# Driver1.net
KiCad netlist of a schematic drawn in Altium Designer
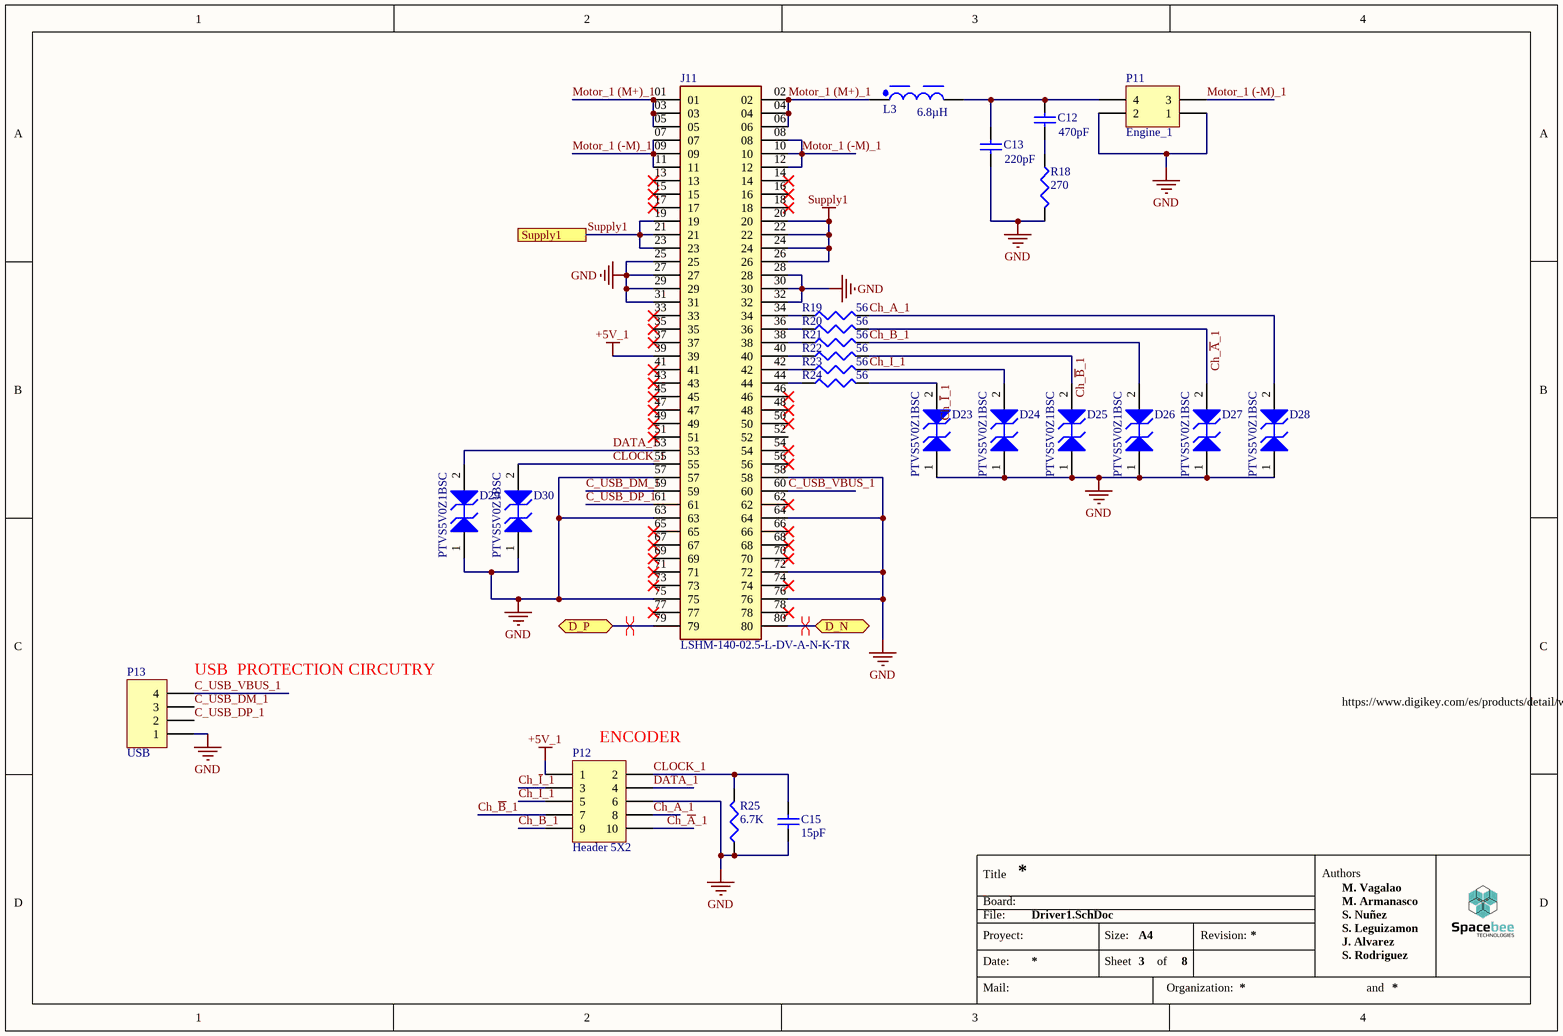
[diagram p0: Driver1.SchDoc]

(export (version "E")
  (design (tool "Eeschema 10.0.6"))
  (components
    (comp (ref "C12")
      (value "470pF")
      (footprint "1608[0603]")
      (description "Capacitor (Semiconductor SIM Model)")
      (fields (field (name "Comment") "Cap Semi") (field (name "PUBLISHER") "Altium Limited"))
      (libsource (lib "Miscellaneous Devices") (part "Cap Semi"))
    )
    (comp (ref "C13")
      (value "220pF")
      (footprint "1608[0603]")
      (description "Capacitor (Semiconductor SIM Model)")
      (fields (field (name "Comment") "Cap Semi") (field (name "PUBLISHER") "Altium Limited"))
      (libsource (lib "Miscellaneous Devices") (part "Cap Semi"))
    )
    (comp (ref "C15")
      (value "15pF")
      (footprint "6-0805_L")
      (description "Capacitor (Semiconductor SIM Model)")
      (fields (field (name "Comment") "Cap Semi") (field (name "PUBLISHER") "Altium Limited"))
      (libsource (lib "SpaceBee") (part "Cap 0805"))
    )
    (comp (ref "D23")
      (value "PTVS5V0Z1BSC")
      (footprint "SOD993B")
      (fields (field (name "MANUFACTURER") "On Semiconductor") (field (name "PARTNUMBER") "1SMB16CAT3"))
      (libsource (lib "DriverLib") (part "PTVS5V0Z1BSC"))
    )
    (comp (ref "D24")
      (value "PTVS5V0Z1BSC")
      (footprint "SOD993B")
      (fields (field (name "MANUFACTURER") "On Semiconductor") (field (name "PARTNUMBER") "1SMB16CAT3"))
      (libsource (lib "DriverLib") (part "PTVS5V0Z1BSC"))
    )
    (comp (ref "D25")
      (value "PTVS5V0Z1BSC")
      (footprint "SOD993B")
      (fields (field (name "MANUFACTURER") "On Semiconductor") (field (name "PARTNUMBER") "1SMB16CAT3"))
      (libsource (lib "DriverLib") (part "PTVS5V0Z1BSC"))
    )
    (comp (ref "D26")
      (value "PTVS5V0Z1BSC")
      (footprint "SOD993B")
      (fields (field (name "MANUFACTURER") "On Semiconductor") (field (name "PARTNUMBER") "1SMB16CAT3"))
      (libsource (lib "DriverLib") (part "PTVS5V0Z1BSC"))
    )
    (comp (ref "D27")
      (value "PTVS5V0Z1BSC")
      (footprint "SOD993B")
      (fields (field (name "MANUFACTURER") "On Semiconductor") (field (name "PARTNUMBER") "1SMB16CAT3"))
      (libsource (lib "DriverLib") (part "PTVS5V0Z1BSC"))
    )
    (comp (ref "D28")
      (value "PTVS5V0Z1BSC")
      (footprint "SOD993B")
      (fields (field (name "MANUFACTURER") "On Semiconductor") (field (name "PARTNUMBER") "1SMB16CAT3"))
      (libsource (lib "DriverLib") (part "PTVS5V0Z1BSC"))
    )
    (comp (ref "D29")
      (value "PTVS5V0Z1BSC")
      (footprint "SOD993B")
      (fields (field (name "MANUFACTURER") "On Semiconductor") (field (name "PARTNUMBER") "1SMB16CAT3"))
      (libsource (lib "DriverLib") (part "PTVS5V0Z1BSC"))
    )
    (comp (ref "D30")
      (value "PTVS5V0Z1BSC")
      (footprint "SOD993B")
      (fields (field (name "MANUFACTURER") "On Semiconductor") (field (name "PARTNUMBER") "1SMB16CAT3"))
      (libsource (lib "DriverLib") (part "PTVS5V0Z1BSC"))
    )
    (comp (ref "J11")
      (value "LSHM-140-02.5-L-DV-A-N-K-TR")
      (footprint "SAMTEC_LSHM-140-02.5-L-DV-A-N-K-TR")
      (description "LSHM - Samtec 0.50mm Razor Beam High-Speed Hermaphroditic Terminal / Socket Strip.")
      (libsource (lib "SpaceBee") (part "LSHM-140-02.5-L-DV-A-N-K-TR"))
    )
    (comp (ref "L3")
      (value "6.8µH")
      (footprint "WE-XHMA_6060")
      (description "WE-XHMA SMD Power Inductor, size 1090, 6.8µH, 10.5A, 7.16mΩ")
      (fields
        (field (name "MANUFACTURER PART NUMBER") "78439369068")
        (field (name "MANUFACTURER") "Wurth Elektronik")
      )
      (libsource (lib "DriverLib") (part "78439369068"))
    )
    (comp (ref "P11")
      (value "Engine_1")
      (footprint "MOLEX_1724480004")
      (description "Header, 2-Pin, Dual row")
      (fields (field (name "PUBLISHER") "Altium Limited"))
      (libsource (lib "SpaceBee") (part "Header 2X2"))
    )
    (comp (ref "P12")
      (value "Header 5X2")
      (footprint "CONN_HIF3FC-14PA-2.54DS(71)_HIR")
      (description "Header, 5-Pin, Dual row")
      (fields (field (name "PUBLISHER") "Altium Limited"))
      (libsource (lib "DriverLib") (part "Header 5X2"))
    )
    (comp (ref "P13")
      (value "USB")
      (footprint "Header 4 SMD")
      (description "Header, 4-Pin")
      (fields (field (name "PUBLISHER") "Altium Limited"))
      (libsource (lib "SpaceBee") (part "Header 4 SMD"))
    )
    (comp (ref "R18")
      (value "270")
      (footprint "J1-0603")
      (description "Resistor")
      (fields (field (name "Comment") "Res3") (field (name "PUBLISHER") "Altium Limited"))
      (libsource (lib "Miscellaneous Devices") (part "Res3"))
    )
    (comp (ref "R19")
      (value "56")
      (footprint "J1-0603")
      (description "Resistor")
      (fields (field (name "Comment") "Res3") (field (name "PUBLISHER") "Altium Limited"))
      (libsource (lib "Miscellaneous Devices") (part "Res3"))
    )
    (comp (ref "R20")
      (value "56")
      (footprint "J1-0603")
      (description "Resistor")
      (fields (field (name "Comment") "Res3") (field (name "PUBLISHER") "Altium Limited"))
      (libsource (lib "Miscellaneous Devices") (part "Res3"))
    )
    (comp (ref "R21")
      (value "56")
      (footprint "J1-0603")
      (description "Resistor")
      (fields (field (name "Comment") "Res3") (field (name "PUBLISHER") "Altium Limited"))
      (libsource (lib "Miscellaneous Devices") (part "Res3"))
    )
    (comp (ref "R22")
      (value "56")
      (footprint "J1-0603")
      (description "Resistor")
      (fields (field (name "Comment") "Res3") (field (name "PUBLISHER") "Altium Limited"))
      (libsource (lib "Miscellaneous Devices") (part "Res3"))
    )
    (comp (ref "R23")
      (value "56")
      (footprint "J1-0603")
      (description "Resistor")
      (fields (field (name "Comment") "Res3") (field (name "PUBLISHER") "Altium Limited"))
      (libsource (lib "Miscellaneous Devices") (part "Res3"))
    )
    (comp (ref "R24")
      (value "56")
      (footprint "J1-0603")
      (description "Resistor")
      (fields (field (name "Comment") "Res3") (field (name "PUBLISHER") "Altium Limited"))
      (libsource (lib "Miscellaneous Devices") (part "Res3"))
    )
    (comp (ref "R25")
      (value "6.7K")
      (footprint "J1-0603")
      (description "Resistor")
      (fields (field (name "Comment") "Res3") (field (name "PUBLISHER") "Altium Limited"))
      (libsource (lib "Miscellaneous Devices") (part "Res3"))
    )
  )
  (nets
    (net (code "1") (name "+5V_1") (class "Default")
      (node (ref "J11") (pin "39") (pinfunction "39_39") (pintype "passive"))
      (node (ref "P12") (pin "1") (pinfunction "1_1") (pintype "passive"))
    )
    (net (code "2") (name "/CLOCK_1") (class "Default")
      (node (ref "C15") (pin "2") (pinfunction "2_2") (pintype "passive"))
      (node (ref "D30") (pin "2") (pinfunction "A2_2") (pintype "passive"))
      (node (ref "J11") (pin "55") (pinfunction "55_55") (pintype "passive"))
      (node (ref "P12") (pin "2") (pinfunction "2_2") (pintype "passive"))
      (node (ref "R25") (pin "2") (pinfunction "2_2") (pintype "passive"))
    )
    (net (code "3") (name "/C_USB_DM_1") (class "Default")
      (node (ref "J11") (pin "59") (pinfunction "59_59") (pintype "passive"))
      (node (ref "P13") (pin "3") (pinfunction "3_3") (pintype "passive"))
    )
    (net (code "4") (name "/C_USB_DP_1") (class "Default")
      (node (ref "J11") (pin "61") (pinfunction "61_61") (pintype "passive"))
      (node (ref "P13") (pin "2") (pinfunction "2_2") (pintype "passive"))
    )
    (net (code "5") (name "/C_USB_VBUS_1") (class "Default")
      (node (ref "J11") (pin "60") (pinfunction "60_60") (pintype "passive"))
      (node (ref "P13") (pin "4") (pinfunction "4_4") (pintype "passive"))
    )
    (net (code "6") (name "/Ch_A_1") (class "Default")
      (node (ref "D28") (pin "2") (pinfunction "A2_2") (pintype "passive"))
      (node (ref "P12") (pin "8") (pinfunction "8_8") (pintype "passive"))
      (node (ref "R19") (pin "2") (pinfunction "2_2") (pintype "passive"))
    )
    (net (code "7") (name "/Ch_B_1") (class "Default")
      (node (ref "D26") (pin "2") (pinfunction "A2_2") (pintype "passive"))
      (node (ref "P12") (pin "9") (pinfunction "9_9") (pintype "passive"))
      (node (ref "R21") (pin "2") (pinfunction "2_2") (pintype "passive"))
    )
    (net (code "8") (name "/Ch_I_1") (class "Default")
      (node (ref "D24") (pin "2") (pinfunction "A2_2") (pintype "passive"))
      (node (ref "P12") (pin "5") (pinfunction "5_5") (pintype "passive"))
      (node (ref "R23") (pin "2") (pinfunction "2_2") (pintype "passive"))
    )
    (net (code "9") (name "/Ch_~{A}_1") (class "Default")
      (node (ref "D27") (pin "2") (pinfunction "A2_2") (pintype "passive"))
      (node (ref "P12") (pin "10") (pinfunction "10_10") (pintype "passive"))
      (node (ref "R20") (pin "2") (pinfunction "2_2") (pintype "passive"))
    )
    (net (code "10") (name "/Ch_~{B}_1") (class "Default")
      (node (ref "D25") (pin "2") (pinfunction "A2_2") (pintype "passive"))
      (node (ref "P12") (pin "7") (pinfunction "7_7") (pintype "passive"))
      (node (ref "R22") (pin "2") (pinfunction "2_2") (pintype "passive"))
    )
    (net (code "11") (name "/Ch_~{I}_1") (class "Default")
      (node (ref "D23") (pin "2") (pinfunction "A2_2") (pintype "passive"))
      (node (ref "P12") (pin "3") (pinfunction "3_3") (pintype "passive"))
      (node (ref "R24") (pin "2") (pinfunction "2_2") (pintype "passive"))
    )
    (net (code "12") (name "/DATA_1") (class "Default")
      (node (ref "D29") (pin "2") (pinfunction "A2_2") (pintype "passive"))
      (node (ref "J11") (pin "53") (pinfunction "53_53") (pintype "passive"))
      (node (ref "P12") (pin "4") (pinfunction "4_4") (pintype "passive"))
    )
    (net (code "13") (name "/D_N") (class "Default")
      (node (ref "J11") (pin "80") (pinfunction "80_80") (pintype "passive"))
    )
    (net (code "14") (name "/D_P") (class "Default")
      (node (ref "J11") (pin "79") (pinfunction "79_79") (pintype "passive"))
    )
    (net (code "15") (name "/Motor_1 (-M)_1") (class "Default")
      (node (ref "J11") (pin "07") (pinfunction "07_07") (pintype "passive"))
      (node (ref "J11") (pin "08") (pinfunction "08_08") (pintype "passive"))
      (node (ref "J11") (pin "09") (pinfunction "09_09") (pintype "passive"))
      (node (ref "J11") (pin "10") (pinfunction "10_10") (pintype "passive"))
      (node (ref "J11") (pin "11") (pinfunction "11_11") (pintype "passive"))
      (node (ref "J11") (pin "12") (pinfunction "12_12") (pintype "passive"))
      (node (ref "P11") (pin "3") (pinfunction "3_3") (pintype "passive"))
    )
    (net (code "16") (name "/Motor_1 (M+)_1") (class "Default")
      (node (ref "J11") (pin "01") (pinfunction "01_01") (pintype "passive"))
      (node (ref "J11") (pin "02") (pinfunction "02_02") (pintype "passive"))
      (node (ref "J11") (pin "03") (pinfunction "03_03") (pintype "passive"))
      (node (ref "J11") (pin "04") (pinfunction "04_04") (pintype "passive"))
      (node (ref "J11") (pin "05") (pinfunction "05_05") (pintype "passive"))
      (node (ref "J11") (pin "06") (pinfunction "06_06") (pintype "passive"))
      (node (ref "L3") (pin "1") (pinfunction "1_1") (pintype "passive"))
    )
    (net (code "17") (name "GND") (class "Default")
      (node (ref "C13") (pin "2") (pinfunction "2_2") (pintype "passive"))
      (node (ref "C15") (pin "1") (pinfunction "1_1") (pintype "passive"))
      (node (ref "D23") (pin "1") (pinfunction "A1_1") (pintype "passive"))
      (node (ref "D24") (pin "1") (pinfunction "A1_1") (pintype "passive"))
      (node (ref "D25") (pin "1") (pinfunction "A1_1") (pintype "passive"))
      (node (ref "D26") (pin "1") (pinfunction "A1_1") (pintype "passive"))
      (node (ref "D27") (pin "1") (pinfunction "A1_1") (pintype "passive"))
      (node (ref "D28") (pin "1") (pinfunction "A1_1") (pintype "passive"))
      (node (ref "D29") (pin "1") (pinfunction "A1_1") (pintype "passive"))
      (node (ref "D30") (pin "1") (pinfunction "A1_1") (pintype "passive"))
      (node (ref "J11") (pin "25") (pinfunction "25_25") (pintype "passive"))
      (node (ref "J11") (pin "27") (pinfunction "27_27") (pintype "passive"))
      (node (ref "J11") (pin "28") (pinfunction "28_28") (pintype "passive"))
      (node (ref "J11") (pin "29") (pinfunction "29_29") (pintype "passive"))
      (node (ref "J11") (pin "30") (pinfunction "30_30") (pintype "passive"))
      (node (ref "J11") (pin "31") (pinfunction "31_31") (pintype "passive"))
      (node (ref "J11") (pin "32") (pinfunction "32_32") (pintype "passive"))
      (node (ref "J11") (pin "57") (pinfunction "57_57") (pintype "passive"))
      (node (ref "J11") (pin "58") (pinfunction "58_58") (pintype "passive"))
      (node (ref "J11") (pin "63") (pinfunction "63_63") (pintype "passive"))
      (node (ref "J11") (pin "64") (pinfunction "64_64") (pintype "passive"))
      (node (ref "J11") (pin "72") (pinfunction "72_72") (pintype "passive"))
      (node (ref "J11") (pin "75") (pinfunction "75_75") (pintype "passive"))
      (node (ref "J11") (pin "76") (pinfunction "76_76") (pintype "passive"))
      (node (ref "P11") (pin "1") (pinfunction "1_1") (pintype "passive"))
      (node (ref "P11") (pin "2") (pinfunction "2_2") (pintype "passive"))
      (node (ref "P12") (pin "6") (pinfunction "6_6") (pintype "passive"))
      (node (ref "P13") (pin "1") (pinfunction "1_1") (pintype "passive"))
      (node (ref "R18") (pin "2") (pinfunction "2_2") (pintype "passive"))
      (node (ref "R25") (pin "1") (pinfunction "1_1") (pintype "passive"))
    )
    (net (code "18") (name "Net-(C12-Pad1)") (class "Default")
      (node (ref "C12") (pin "1") (pinfunction "1_1") (pintype "passive"))
      (node (ref "C13") (pin "1") (pinfunction "1_1") (pintype "passive"))
      (node (ref "L3") (pin "2") (pinfunction "2_2") (pintype "passive"))
      (node (ref "P11") (pin "4") (pinfunction "4_4") (pintype "passive"))
    )
    (net (code "19") (name "Net-(C12-Pad2)") (class "Default")
      (node (ref "C12") (pin "2") (pinfunction "2_2") (pintype "passive"))
      (node (ref "R18") (pin "1") (pinfunction "1_1") (pintype "passive"))
    )
    (net (code "20") (name "Net-(J11-Pad34)") (class "Default")
      (node (ref "J11") (pin "34") (pinfunction "34_34") (pintype "passive"))
      (node (ref "R19") (pin "1") (pinfunction "1_1") (pintype "passive"))
    )
    (net (code "21") (name "Net-(J11-Pad36)") (class "Default")
      (node (ref "J11") (pin "36") (pinfunction "36_36") (pintype "passive"))
      (node (ref "R20") (pin "1") (pinfunction "1_1") (pintype "passive"))
    )
    (net (code "22") (name "Net-(J11-Pad38)") (class "Default")
      (node (ref "J11") (pin "38") (pinfunction "38_38") (pintype "passive"))
      (node (ref "R21") (pin "1") (pinfunction "1_1") (pintype "passive"))
    )
    (net (code "23") (name "Net-(J11-Pad40)") (class "Default")
      (node (ref "J11") (pin "40") (pinfunction "40_40") (pintype "passive"))
      (node (ref "R22") (pin "1") (pinfunction "1_1") (pintype "passive"))
    )
    (net (code "24") (name "Net-(J11-Pad42)") (class "Default")
      (node (ref "J11") (pin "42") (pinfunction "42_42") (pintype "passive"))
      (node (ref "R23") (pin "1") (pinfunction "1_1") (pintype "passive"))
    )
    (net (code "25") (name "Net-(J11-Pad44)") (class "Default")
      (node (ref "J11") (pin "44") (pinfunction "44_44") (pintype "passive"))
      (node (ref "R24") (pin "1") (pinfunction "1_1") (pintype "passive"))
    )
    (net (code "26") (name "Supply1") (class "Default")
      (node (ref "J11") (pin "19") (pinfunction "19_19") (pintype "passive"))
      (node (ref "J11") (pin "20") (pinfunction "20_20") (pintype "passive"))
      (node (ref "J11") (pin "21") (pinfunction "21_21") (pintype "passive"))
      (node (ref "J11") (pin "22") (pinfunction "22_22") (pintype "passive"))
      (node (ref "J11") (pin "23") (pinfunction "23_23") (pintype "passive"))
      (node (ref "J11") (pin "24") (pinfunction "24_24") (pintype "passive"))
      (node (ref "J11") (pin "26") (pinfunction "26_26") (pintype "passive"))
    )
    (net (code "27") (name "unconnected-(J11-Pad13)") (class "Default")
      (node (ref "J11") (pin "13") (pinfunction "13_13") (pintype "passive+no_connect"))
    )
    (net (code "28") (name "unconnected-(J11-Pad14)") (class "Default")
      (node (ref "J11") (pin "14") (pinfunction "14_14") (pintype "passive+no_connect"))
    )
    (net (code "29") (name "unconnected-(J11-Pad15)") (class "Default")
      (node (ref "J11") (pin "15") (pinfunction "15_15") (pintype "passive+no_connect"))
    )
    (net (code "30") (name "unconnected-(J11-Pad16)") (class "Default")
      (node (ref "J11") (pin "16") (pinfunction "16_16") (pintype "passive+no_connect"))
    )
    (net (code "31") (name "unconnected-(J11-Pad17)") (class "Default")
      (node (ref "J11") (pin "17") (pinfunction "17_17") (pintype "passive+no_connect"))
    )
    (net (code "32") (name "unconnected-(J11-Pad18)") (class "Default")
      (node (ref "J11") (pin "18") (pinfunction "18_18") (pintype "passive+no_connect"))
    )
    (net (code "33") (name "unconnected-(J11-Pad33)") (class "Default")
      (node (ref "J11") (pin "33") (pinfunction "33_33") (pintype "passive+no_connect"))
    )
    (net (code "34") (name "unconnected-(J11-Pad35)") (class "Default")
      (node (ref "J11") (pin "35") (pinfunction "35_35") (pintype "passive+no_connect"))
    )
    (net (code "35") (name "unconnected-(J11-Pad37)") (class "Default")
      (node (ref "J11") (pin "37") (pinfunction "37_37") (pintype "passive+no_connect"))
    )
    (net (code "36") (name "unconnected-(J11-Pad41)") (class "Default")
      (node (ref "J11") (pin "41") (pinfunction "41_41") (pintype "passive+no_connect"))
    )
    (net (code "37") (name "unconnected-(J11-Pad43)") (class "Default")
      (node (ref "J11") (pin "43") (pinfunction "43_43") (pintype "passive+no_connect"))
    )
    (net (code "38") (name "unconnected-(J11-Pad45)") (class "Default")
      (node (ref "J11") (pin "45") (pinfunction "45_45") (pintype "passive+no_connect"))
    )
    (net (code "39") (name "unconnected-(J11-Pad46)") (class "Default")
      (node (ref "J11") (pin "46") (pinfunction "46_46") (pintype "passive+no_connect"))
    )
    (net (code "40") (name "unconnected-(J11-Pad47)") (class "Default")
      (node (ref "J11") (pin "47") (pinfunction "47_47") (pintype "passive+no_connect"))
    )
    (net (code "41") (name "unconnected-(J11-Pad48)") (class "Default")
      (node (ref "J11") (pin "48") (pinfunction "48_48") (pintype "passive+no_connect"))
    )
    (net (code "42") (name "unconnected-(J11-Pad49)") (class "Default")
      (node (ref "J11") (pin "49") (pinfunction "49_49") (pintype "passive+no_connect"))
    )
    (net (code "43") (name "unconnected-(J11-Pad50)") (class "Default")
      (node (ref "J11") (pin "50") (pinfunction "50_50") (pintype "passive+no_connect"))
    )
    (net (code "44") (name "unconnected-(J11-Pad51)") (class "Default")
      (node (ref "J11") (pin "51") (pinfunction "51_51") (pintype "passive+no_connect"))
    )
    (net (code "45") (name "unconnected-(J11-Pad52)") (class "Default")
      (node (ref "J11") (pin "52") (pinfunction "52_52") (pintype "passive"))
    )
    (net (code "46") (name "unconnected-(J11-Pad54)") (class "Default")
      (node (ref "J11") (pin "54") (pinfunction "54_54") (pintype "passive+no_connect"))
    )
    (net (code "47") (name "unconnected-(J11-Pad56)") (class "Default")
      (node (ref "J11") (pin "56") (pinfunction "56_56") (pintype "passive+no_connect"))
    )
    (net (code "48") (name "unconnected-(J11-Pad62)") (class "Default")
      (node (ref "J11") (pin "62") (pinfunction "62_62") (pintype "passive+no_connect"))
    )
    (net (code "49") (name "unconnected-(J11-Pad65)") (class "Default")
      (node (ref "J11") (pin "65") (pinfunction "65_65") (pintype "passive+no_connect"))
    )
    (net (code "50") (name "unconnected-(J11-Pad66)") (class "Default")
      (node (ref "J11") (pin "66") (pinfunction "66_66") (pintype "passive+no_connect"))
    )
    (net (code "51") (name "unconnected-(J11-Pad67)") (class "Default")
      (node (ref "J11") (pin "67") (pinfunction "67_67") (pintype "passive+no_connect"))
    )
    (net (code "52") (name "unconnected-(J11-Pad68)") (class "Default")
      (node (ref "J11") (pin "68") (pinfunction "68_68") (pintype "passive+no_connect"))
    )
    (net (code "53") (name "unconnected-(J11-Pad69)") (class "Default")
      (node (ref "J11") (pin "69") (pinfunction "69_69") (pintype "passive+no_connect"))
    )
    (net (code "54") (name "unconnected-(J11-Pad70)") (class "Default")
      (node (ref "J11") (pin "70") (pinfunction "70_70") (pintype "passive+no_connect"))
    )
    (net (code "55") (name "unconnected-(J11-Pad71)") (class "Default")
      (node (ref "J11") (pin "71") (pinfunction "71_71") (pintype "passive+no_connect"))
    )
    (net (code "56") (name "unconnected-(J11-Pad73)") (class "Default")
      (node (ref "J11") (pin "73") (pinfunction "73_73") (pintype "passive+no_connect"))
    )
    (net (code "57") (name "unconnected-(J11-Pad74)") (class "Default")
      (node (ref "J11") (pin "74") (pinfunction "74_74") (pintype "passive+no_connect"))
    )
    (net (code "58") (name "unconnected-(J11-Pad77)") (class "Default")
      (node (ref "J11") (pin "77") (pinfunction "77_77") (pintype "passive+no_connect"))
    )
    (net (code "59") (name "unconnected-(J11-Pad78)") (class "Default")
      (node (ref "J11") (pin "78") (pinfunction "78_78") (pintype "passive+no_connect"))
    )
  )
)
